# TopSCH.net
KiCad netlist of a schematic drawn in Altium Designer
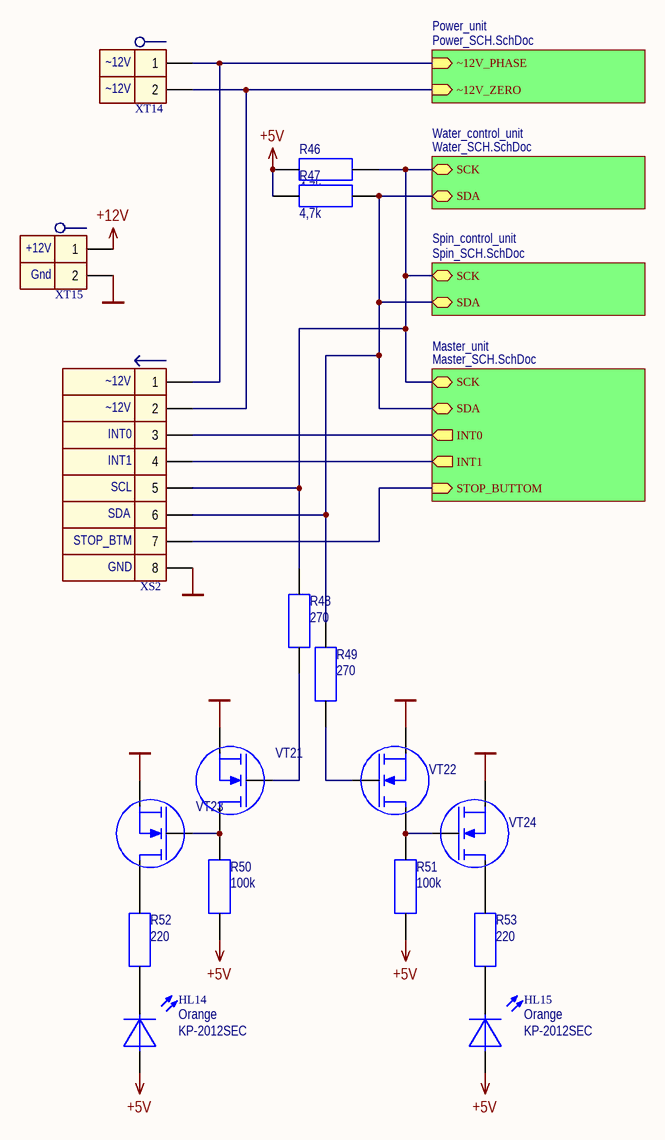
[diagram p0: TopSCH.SchDoc]

(export (version "E")
  (design (tool "Eeschema 10.0.6"))
  (components
    (comp (ref "HL14")
      (value "Orange")
      (footprint "Indicator:DIOMELF2012M")
      (description "Diod LED SMD Orange")
      (fields (field (name "MANUFACTURERPARTNUMBER") "KP-2012SEC"))
      (libsource (lib "Indicator") (part "LED1_O"))
    )
    (comp (ref "HL15")
      (value "Orange")
      (footprint "Indicator:DIOMELF2012M")
      (description "Diod LED SMD Orange")
      (fields (field (name "MANUFACTURERPARTNUMBER") "KP-2012SEC"))
      (libsource (lib "Indicator") (part "LED1_O"))
    )
    (comp (ref "R46")
      (value "4,7k")
      (footprint "SMDRC0805")
      (description "Generic resistor")
      (fields (field (name "PARTNUMBER") "Resistor 0805 4,7k"))
      (libsource (lib "library") (part "Resistor"))
    )
    (comp (ref "R47")
      (value "4,7k")
      (footprint "SMDRC0805")
      (description "Generic resistor")
      (fields (field (name "PARTNUMBER") "Resistor 0805 4,7k"))
      (libsource (lib "library") (part "Resistor"))
    )
    (comp (ref "R48")
      (value "270")
      (footprint "SMDRC0805")
      (description "Generic resistor")
      (fields (field (name "PARTNUMBER") "Resistor 0805 270"))
      (libsource (lib "") (part "Resistor_1"))
    )
    (comp (ref "R49")
      (value "270")
      (footprint "SMDRC0805")
      (description "Generic resistor")
      (fields (field (name "PARTNUMBER") "Resistor 0805 270"))
      (libsource (lib "") (part "Resistor_1"))
    )
    (comp (ref "R50")
      (value "100k")
      (footprint "SMDRC0805")
      (description "Generic resistor")
      (fields (field (name "PARTNUMBER") "Resistor 0805 100k"))
      (libsource (lib "") (part "Resistor_2"))
    )
    (comp (ref "R51")
      (value "100k")
      (footprint "SMDRC0805")
      (description "Generic resistor")
      (fields (field (name "PARTNUMBER") "Resistor 0805 100k"))
      (libsource (lib "library") (part "Resistor"))
    )
    (comp (ref "R52")
      (value "220")
      (footprint "SMDRC0805")
      (description "Generic resistor")
      (fields (field (name "PARTNUMBER") "Resistor 0805 220"))
      (libsource (lib "library") (part "Resistor"))
    )
    (comp (ref "R53")
      (value "220")
      (footprint "SMDRC0805")
      (description "Generic resistor")
      (fields (field (name "PARTNUMBER") "Resistor 0805 220"))
      (libsource (lib "") (part "Resistor_2"))
    )
    (comp (ref "VT21")
      (value "2N7002")
      (footprint "Standard:SOT23 (TO-236AB)")
      (description "60V, 300mA N-channel Trench MOSFET")
      (libsource (lib "Transistor") (part "2N7002 n-MOSFET"))
    )
    (comp (ref "VT22")
      (value "2N7002")
      (footprint "Standard:SOT23 (TO-236AB)")
      (description "60V, 300mA N-channel Trench MOSFET")
      (libsource (lib "Transistor") (part "2N7002 n-MOSFET"))
    )
    (comp (ref "VT23")
      (value "2N7002")
      (footprint "Standard:SOT23 (TO-236AB)")
      (description "60V, 300mA N-channel Trench MOSFET")
      (libsource (lib "Transistor") (part "2N7002 n-MOSFET"))
    )
    (comp (ref "VT24")
      (value "2N7002")
      (footprint "Standard:SOT23 (TO-236AB)")
      (description "60V, 300mA N-channel Trench MOSFET")
      (libsource (lib "Transistor") (part "2N7002 n-MOSFET"))
    )
    (comp (ref "XS2")
      (value "PLS-08R")
      (footprint "Connector:PLS-08R1")
      (description "Male 8-pin connection")
      (libsource (lib "Connector") (part "Con8_M PLS-08MR"))
    )
    (comp (ref "XT14")
      (value "330-021-12")
      (footprint "Connector:330-021-12")
      (description "Demountable connection  2-pin")
      (fields (field (name "MANUFACTURER") "Degson Electronics Co., Ltd"))
      (libsource (lib "Connector") (part "Con2_D 330-021-12"))
    )
    (comp (ref "XT15")
      (value "330-021-12")
      (footprint "Connector:330-021-12")
      (description "Demountable connection  2-pin")
      (fields (field (name "MANUFACTURER") "Degson Electronics Co., Ltd"))
      (libsource (lib "Connector") (part "Con2_D 330-021-12"))
    )
  )
  (nets
    (net (code "1") (name "+5V") (class "Default")
      (node (ref "HL14") (pin "1") (pinfunction "1_1") (pintype "passive"))
      (node (ref "HL15") (pin "1") (pinfunction "1_1") (pintype "passive"))
      (node (ref "R46") (pin "2") (pinfunction "2_2") (pintype "passive"))
      (node (ref "R47") (pin "2") (pinfunction "2_2") (pintype "passive"))
      (node (ref "R50") (pin "2") (pinfunction "2_2") (pintype "passive"))
      (node (ref "R51") (pin "2") (pinfunction "2_2") (pintype "passive"))
    )
    (net (code "2") (name "+12V") (class "Default")
      (node (ref "XT15") (pin "1") (pinfunction "1_1") (pintype "passive"))
    )
    (net (code "3") (name "/INT0") (class "Default")
      (node (ref "XS2") (pin "3") (pinfunction "3_3") (pintype "passive"))
    )
    (net (code "4") (name "/INT1") (class "Default")
      (node (ref "XS2") (pin "4") (pinfunction "4_4") (pintype "passive"))
    )
    (net (code "5") (name "/SCK") (class "Default")
      (node (ref "R46") (pin "1") (pinfunction "1_1") (pintype "passive"))
      (node (ref "R48") (pin "2") (pinfunction "2_2") (pintype "passive"))
      (node (ref "XS2") (pin "5") (pinfunction "5_5") (pintype "passive"))
    )
    (net (code "6") (name "/SDA") (class "Default")
      (node (ref "R47") (pin "1") (pinfunction "1_1") (pintype "passive"))
      (node (ref "R49") (pin "2") (pinfunction "2_2") (pintype "passive"))
      (node (ref "XS2") (pin "6") (pinfunction "6_6") (pintype "passive"))
    )
    (net (code "7") (name "/STOP_BUTTOM") (class "Default")
      (node (ref "XS2") (pin "7") (pinfunction "7_7") (pintype "passive"))
    )
    (net (code "8") (name "/~12V_PHASE") (class "Default")
      (node (ref "XS2") (pin "1") (pinfunction "1_1") (pintype "passive"))
      (node (ref "XT14") (pin "1") (pinfunction "1_1") (pintype "passive"))
    )
    (net (code "9") (name "/~12V_ZERO") (class "Default")
      (node (ref "XS2") (pin "2") (pinfunction "2_2") (pintype "passive"))
      (node (ref "XT14") (pin "2") (pinfunction "2_2") (pintype "passive"))
    )
    (net (code "10") (name "GND") (class "Default")
      (node (ref "VT21") (pin "2") (pinfunction "S_2") (pintype "passive"))
      (node (ref "VT22") (pin "2") (pinfunction "S_2") (pintype "passive"))
      (node (ref "VT23") (pin "2") (pinfunction "S_2") (pintype "passive"))
      (node (ref "VT24") (pin "2") (pinfunction "S_2") (pintype "passive"))
      (node (ref "XS2") (pin "8") (pinfunction "8_8") (pintype "passive"))
      (node (ref "XT15") (pin "2") (pinfunction "2_2") (pintype "passive"))
    )
    (net (code "11") (name "Net-(HL14-Pad2)") (class "Default")
      (node (ref "HL14") (pin "2") (pinfunction "2_2") (pintype "passive"))
      (node (ref "R52") (pin "2") (pinfunction "2_2") (pintype "passive"))
    )
    (net (code "12") (name "Net-(HL15-Pad2)") (class "Default")
      (node (ref "HL15") (pin "2") (pinfunction "2_2") (pintype "passive"))
      (node (ref "R53") (pin "2") (pinfunction "2_2") (pintype "passive"))
    )
    (net (code "13") (name "Net-(VT21-D)") (class "Default")
      (node (ref "R50") (pin "1") (pinfunction "1_1") (pintype "passive"))
      (node (ref "VT21") (pin "3") (pinfunction "D_3") (pintype "passive"))
      (node (ref "VT23") (pin "1") (pinfunction "G_1") (pintype "passive"))
    )
    (net (code "14") (name "Net-(VT21-G)") (class "Default")
      (node (ref "R48") (pin "1") (pinfunction "1_1") (pintype "passive"))
      (node (ref "VT21") (pin "1") (pinfunction "G_1") (pintype "passive"))
    )
    (net (code "15") (name "Net-(VT22-D)") (class "Default")
      (node (ref "R51") (pin "1") (pinfunction "1_1") (pintype "passive"))
      (node (ref "VT22") (pin "3") (pinfunction "D_3") (pintype "passive"))
      (node (ref "VT24") (pin "1") (pinfunction "G_1") (pintype "passive"))
    )
    (net (code "16") (name "Net-(VT22-G)") (class "Default")
      (node (ref "R49") (pin "1") (pinfunction "1_1") (pintype "passive"))
      (node (ref "VT22") (pin "1") (pinfunction "G_1") (pintype "passive"))
    )
    (net (code "17") (name "Net-(VT23-D)") (class "Default")
      (node (ref "R52") (pin "1") (pinfunction "1_1") (pintype "passive"))
      (node (ref "VT23") (pin "3") (pinfunction "D_3") (pintype "passive"))
    )
    (net (code "18") (name "Net-(VT24-D)") (class "Default")
      (node (ref "R53") (pin "1") (pinfunction "1_1") (pintype "passive"))
      (node (ref "VT24") (pin "3") (pinfunction "D_3") (pintype "passive"))
    )
  )
)
